# Power_Supply.net
KiCad netlist of a schematic drawn in Altium Designer
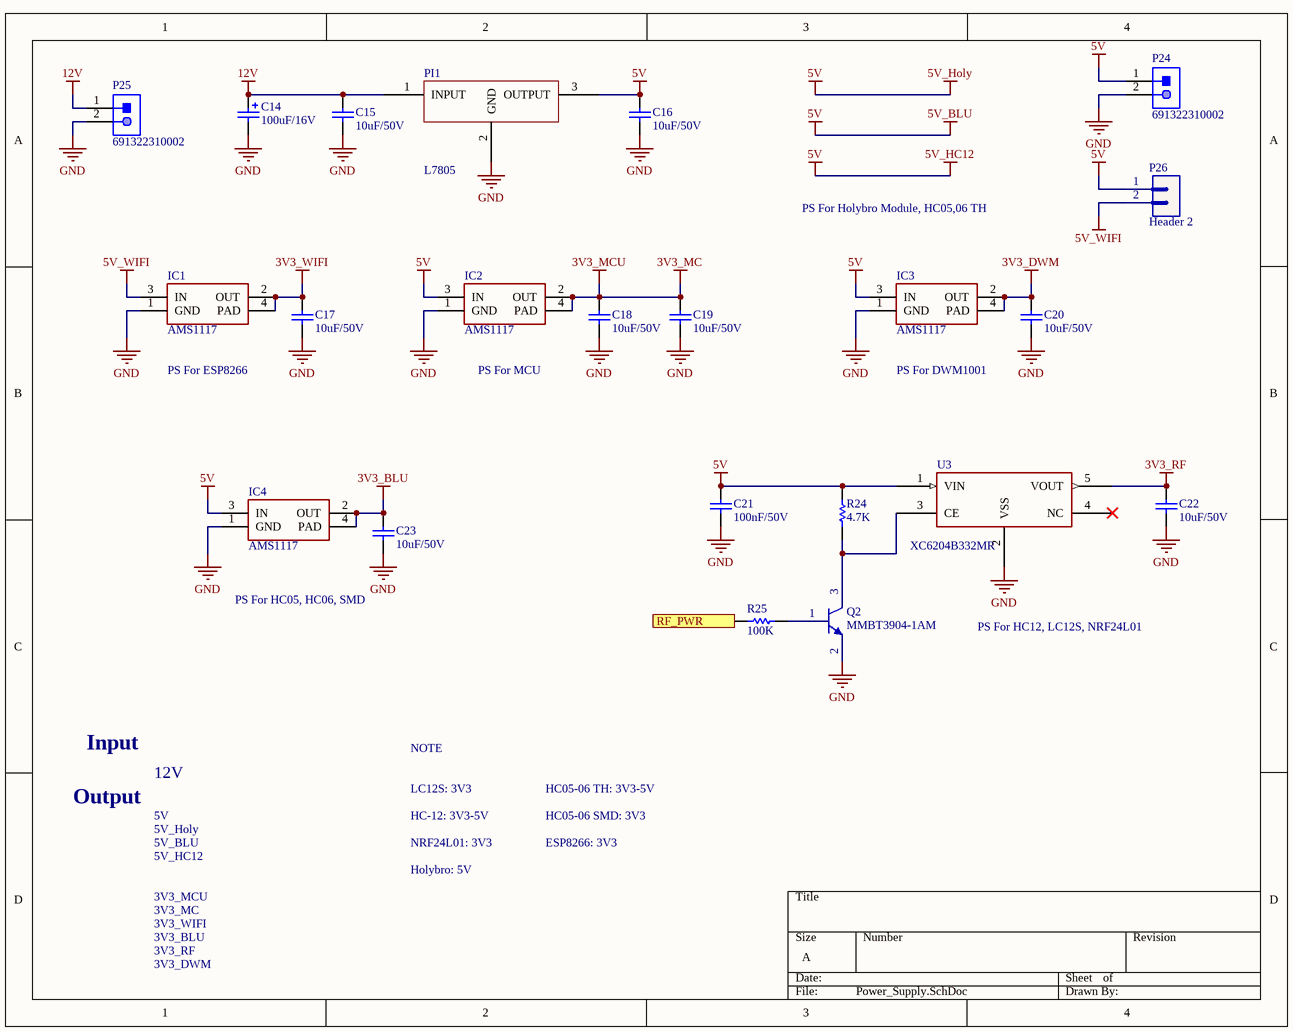
[diagram p0: Power_Supply.SchDoc]

(export (version "E")
  (design (tool "Eeschema 10.0.6"))
  (components
    (comp (ref "C14")
      (value "100uF/16V")
      (footprint "CAP-SM-AL-SIZE-D-D6L6")
      (description "CAP ALUM 100UF 20% 16V SMD")
      (fields
        (field (name "MANUFACTURER") "Nichicon")
        (field (name "MANUFACTURER PART NUMBER") "UWX1C101MCL1GB")
      )
      (libsource (lib "Capacitor") (part "Cap-Al-100uF-16V-D6L5"))
    )
    (comp (ref "C15")
      (value "10uF/50V")
      (footprint "CAP-SM-0805")
      (description "CAP CER 10UF 50V X5R 0805")
      (fields
        (field (name "MANUFACTURER") "Yageo")
        (field (name "MANUFACTURER PART NUMBER") "CC0805KKX5R9BB106")
      )
      (libsource (lib "Capacitor") (part "Cap-10uF-50V-0805"))
    )
    (comp (ref "C16")
      (value "10uF/50V")
      (footprint "CAP-SM-0805")
      (description "CAP CER 10UF 50V X5R 0805")
      (fields
        (field (name "MANUFACTURER") "Yageo")
        (field (name "MANUFACTURER PART NUMBER") "CC0805KKX5R9BB106")
      )
      (libsource (lib "Capacitor") (part "Cap-10uF-50V-0805"))
    )
    (comp (ref "C17")
      (value "10uF/50V")
      (footprint "CAP-SM-0805")
      (description "CAP CER 10UF 50V X5R 0805")
      (fields
        (field (name "MANUFACTURER") "Yageo")
        (field (name "MANUFACTURER PART NUMBER") "CC0805KKX5R9BB106")
      )
      (libsource (lib "Capacitor") (part "Cap-10uF-50V-0805"))
    )
    (comp (ref "C18")
      (value "10uF/50V")
      (footprint "CAP-SM-0805")
      (description "CAP CER 10UF 50V X5R 0805")
      (fields
        (field (name "MANUFACTURER") "Yageo")
        (field (name "MANUFACTURER PART NUMBER") "CC0805KKX5R9BB106")
      )
      (libsource (lib "Capacitor") (part "Cap-10uF-50V-0805"))
    )
    (comp (ref "C19")
      (value "10uF/50V")
      (footprint "CAP-SM-0805")
      (description "CAP CER 10UF 50V X5R 0805")
      (fields
        (field (name "MANUFACTURER") "Yageo")
        (field (name "MANUFACTURER PART NUMBER") "CC0805KKX5R9BB106")
      )
      (libsource (lib "Capacitor") (part "Cap-10uF-50V-0805"))
    )
    (comp (ref "C20")
      (value "10uF/50V")
      (footprint "CAP-SM-0805")
      (description "CAP CER 10UF 50V X5R 0805")
      (fields
        (field (name "MANUFACTURER") "Yageo")
        (field (name "MANUFACTURER PART NUMBER") "CC0805KKX5R9BB106")
      )
      (libsource (lib "Capacitor") (part "Cap-10uF-50V-0805"))
    )
    (comp (ref "C21")
      (value "100nF/50V")
      (footprint "CAP-SM-0805")
      (description "CAP CER 0.1UF 50V Y5V 0805")
      (fields
        (field (name "MANUFACTURER") "Samsung Electro-Mechanics")
        (field (name "MANUFACTURER PART NUMBER") "CL21F104ZBCNNNC")
      )
      (libsource (lib "Capacitor") (part "Cap-100nF-50V-0805"))
    )
    (comp (ref "C22")
      (value "10uF/50V")
      (footprint "CAP-SM-0805")
      (description "CAP CER 10UF 50V X5R 0805")
      (fields
        (field (name "MANUFACTURER") "Yageo")
        (field (name "MANUFACTURER PART NUMBER") "CC0805KKX5R9BB106")
      )
      (libsource (lib "Capacitor") (part "Cap-10uF-50V-0805"))
    )
    (comp (ref "C23")
      (value "10uF/50V")
      (footprint "CAP-SM-0805")
      (description "CAP CER 10UF 50V X5R 0805")
      (fields
        (field (name "MANUFACTURER") "Yageo")
        (field (name "MANUFACTURER PART NUMBER") "CC0805KKX5R9BB106")
      )
      (libsource (lib "Capacitor") (part "Cap-10uF-50V-0805"))
    )
    (comp (ref "IC1")
      (value "AMS1117")
      (footprint "SOT223")
      (description "Available in 1.8V, 2.5V, 2.85V, 3.3V, 5V, and  Adjustable Versions")
      (libsource (lib "PI") (part "AMS1117"))
    )
    (comp (ref "IC2")
      (value "AMS1117")
      (footprint "SOT223")
      (description "Available in 1.8V, 2.5V, 2.85V, 3.3V, 5V, and  Adjustable Versions")
      (libsource (lib "PI") (part "AMS1117"))
    )
    (comp (ref "IC3")
      (value "AMS1117")
      (footprint "SOT223")
      (description "Available in 1.8V, 2.5V, 2.85V, 3.3V, 5V, and  Adjustable Versions")
      (libsource (lib "PI") (part "AMS1117"))
    )
    (comp (ref "IC4")
      (value "AMS1117")
      (footprint "SOT223")
      (description "Available in 1.8V, 2.5V, 2.85V, 3.3V, 5V, and  Adjustable Versions")
      (libsource (lib "PI") (part "AMS1117"))
    )
    (comp (ref "P24")
      (value "691322310002")
      (footprint "691322310002")
      (description "WR-TBL Serie 322 Horizontal PCB Header, Pluggable, pitch 3.81mm, 2p")
      (fields (field (name "PUBLISHER") "Wurth Elektronik"))
      (libsource (lib "o162719v243 Altium_WR-TBL (rev19a)") (part "691322310002"))
    )
    (comp (ref "P25")
      (value "691322310002")
      (footprint "691322310002")
      (description "WR-TBL Serie 322 Horizontal PCB Header, Pluggable, pitch 3.81mm, 2p")
      (fields (field (name "PUBLISHER") "Wurth Elektronik"))
      (libsource (lib "o162719v243 Altium_WR-TBL (rev19a)") (part "691322310002"))
    )
    (comp (ref "P26")
      (value "Header 2")
      (footprint "JP2")
      (description "Header, 2-Pin")
      (fields (field (name "PUBLISHER") "Altium Limited"))
      (libsource (lib "Header-connector") (part "Header 2"))
    )
    (comp (ref "PI1") (value "L7805") (footprint "L7805_SMD") (libsource (lib "chicken") (part "L7805")))
    (comp (ref "Q2")
      (value "MMBT3904-1AM")
      (footprint "SOT23_NEX")
      (libsource (lib "BJT") (part "MMBT3904-1AM"))
    )
    (comp (ref "R24")
      (value "4.7K")
      (footprint "Resistor:RES-SM-0805")
      (description "RES SMD 4.7K OHM 5% 1/8W 0805")
      (fields
        (field (name "MANUFACTURER") "Yageo")
        (field (name "MANUFACTURER PART NUMBER") "RC0805JR-074K7L")
      )
      (libsource (lib "Resistor") (part "Res-4.7K-0805"))
    )
    (comp (ref "R25")
      (value "100K")
      (footprint "Resistor:RES-SM-0805")
      (description "RES 0 OHM JUMPER 0805")
      (fields
        (field (name "MANUFACTURER") "Vishay Dale")
        (field (name "MANUFACTURER PART NUMBER") "WSL080500000ZEA9")
      )
      (libsource (lib "Resistor") (part "Res-100K-0805"))
    )
    (comp (ref "U3")
      (value "XC6204B332MR")
      (footprint "XC6204/05_SOT-00")
      (fields (field (name "COPYRIGHT") "Copyright (C) 2018 Accelerated Designs. All rights reserved"))
      (libsource (lib "PI") (part "XC6204B332MR"))
    )
  )
  (nets
    (net (code "1") (name "/RF_PWR") (class "Default")
      (node (ref "R25") (pin "1") (pinfunction "1_1") (pintype "passive"))
    )
    (net (code "2") (name "3V3_BLU") (class "Default")
      (node (ref "C23") (pin "2") (pinfunction "2_2") (pintype "passive"))
      (node (ref "IC4") (pin "2") (pinfunction "OUT_2") (pintype "passive"))
      (node (ref "IC4") (pin "4") (pinfunction "PAD_4") (pintype "passive"))
    )
    (net (code "3") (name "3V3_DWM") (class "Default")
      (node (ref "C20") (pin "2") (pinfunction "2_2") (pintype "passive"))
      (node (ref "IC3") (pin "2") (pinfunction "OUT_2") (pintype "passive"))
      (node (ref "IC3") (pin "4") (pinfunction "PAD_4") (pintype "passive"))
    )
    (net (code "4") (name "3V3_MC") (class "Default")
      (node (ref "C18") (pin "2") (pinfunction "2_2") (pintype "passive"))
      (node (ref "C19") (pin "2") (pinfunction "2_2") (pintype "passive"))
      (node (ref "IC2") (pin "2") (pinfunction "OUT_2") (pintype "passive"))
      (node (ref "IC2") (pin "4") (pinfunction "PAD_4") (pintype "passive"))
    )
    (net (code "5") (name "3V3_RF") (class "Default")
      (node (ref "C22") (pin "2") (pinfunction "2_2") (pintype "passive"))
      (node (ref "U3") (pin "5") (pinfunction "VOUT_5") (pintype "output"))
    )
    (net (code "6") (name "3V3_WIFI") (class "Default")
      (node (ref "C17") (pin "2") (pinfunction "2_2") (pintype "passive"))
      (node (ref "IC1") (pin "2") (pinfunction "OUT_2") (pintype "passive"))
      (node (ref "IC1") (pin "4") (pinfunction "PAD_4") (pintype "passive"))
    )
    (net (code "7") (name "5V") (class "Default")
      (node (ref "C16") (pin "2") (pinfunction "2_2") (pintype "passive"))
      (node (ref "C21") (pin "2") (pinfunction "2_2") (pintype "passive"))
      (node (ref "IC2") (pin "3") (pinfunction "IN_3") (pintype "passive"))
      (node (ref "IC3") (pin "3") (pinfunction "IN_3") (pintype "passive"))
      (node (ref "IC4") (pin "3") (pinfunction "IN_3") (pintype "passive"))
      (node (ref "P24") (pin "1") (pinfunction "1_1") (pintype "passive"))
      (node (ref "P26") (pin "1") (pinfunction "1_1") (pintype "passive"))
      (node (ref "PI1") (pin "3") (pinfunction "OUTPUT_3") (pintype "passive"))
      (node (ref "R24") (pin "2") (pinfunction "2_2") (pintype "passive"))
      (node (ref "U3") (pin "1") (pinfunction "VIN_1") (pintype "input"))
    )
    (net (code "8") (name "5V_WIFI") (class "Default")
      (node (ref "IC1") (pin "3") (pinfunction "IN_3") (pintype "passive"))
      (node (ref "P26") (pin "2") (pinfunction "2_2") (pintype "passive"))
    )
    (net (code "9") (name "12V") (class "Default")
      (node (ref "C14") (pin "1") (pinfunction "1_1") (pintype "passive"))
      (node (ref "C15") (pin "2") (pinfunction "2_2") (pintype "passive"))
      (node (ref "P25") (pin "1") (pinfunction "1_1") (pintype "passive"))
      (node (ref "PI1") (pin "1") (pinfunction "INPUT_1") (pintype "passive"))
    )
    (net (code "10") (name "GND") (class "Default")
      (node (ref "C14") (pin "2") (pinfunction "2_2") (pintype "passive"))
      (node (ref "C15") (pin "1") (pinfunction "1_1") (pintype "passive"))
      (node (ref "C16") (pin "1") (pinfunction "1_1") (pintype "passive"))
      (node (ref "C17") (pin "1") (pinfunction "1_1") (pintype "passive"))
      (node (ref "C18") (pin "1") (pinfunction "1_1") (pintype "passive"))
      (node (ref "C19") (pin "1") (pinfunction "1_1") (pintype "passive"))
      (node (ref "C20") (pin "1") (pinfunction "1_1") (pintype "passive"))
      (node (ref "C21") (pin "1") (pinfunction "1_1") (pintype "passive"))
      (node (ref "C22") (pin "1") (pinfunction "1_1") (pintype "passive"))
      (node (ref "C23") (pin "1") (pinfunction "1_1") (pintype "passive"))
      (node (ref "IC1") (pin "1") (pinfunction "GND_1") (pintype "passive"))
      (node (ref "IC2") (pin "1") (pinfunction "GND_1") (pintype "passive"))
      (node (ref "IC3") (pin "1") (pinfunction "GND_1") (pintype "passive"))
      (node (ref "IC4") (pin "1") (pinfunction "GND_1") (pintype "passive"))
      (node (ref "P24") (pin "2") (pinfunction "2_2") (pintype "passive"))
      (node (ref "P25") (pin "2") (pinfunction "2_2") (pintype "passive"))
      (node (ref "PI1") (pin "2") (pinfunction "GND_2") (pintype "passive"))
      (node (ref "Q2") (pin "2") (pinfunction "E_2") (pintype "passive"))
      (node (ref "U3") (pin "2") (pinfunction "VSS_2") (pintype "passive"))
    )
    (net (code "11") (name "Net-(Q2-B)") (class "Default")
      (node (ref "Q2") (pin "1") (pinfunction "B_1") (pintype "passive"))
      (node (ref "R25") (pin "2") (pinfunction "2_2") (pintype "passive"))
    )
    (net (code "12") (name "Net-(Q2-C)") (class "Default")
      (node (ref "Q2") (pin "3") (pinfunction "C_3") (pintype "passive"))
      (node (ref "R24") (pin "1") (pinfunction "1_1") (pintype "passive"))
      (node (ref "U3") (pin "3") (pinfunction "CE_3") (pintype "passive"))
    )
    (net (code "13") (name "unconnected-(U3-NC-Pad4)") (class "Default")
      (node (ref "U3") (pin "4") (pinfunction "NC_4") (pintype "passive+no_connect"))
    )
  )
)
